# Ambient_Light_Sensor.net
KiCad netlist of a schematic drawn in Altium Designer
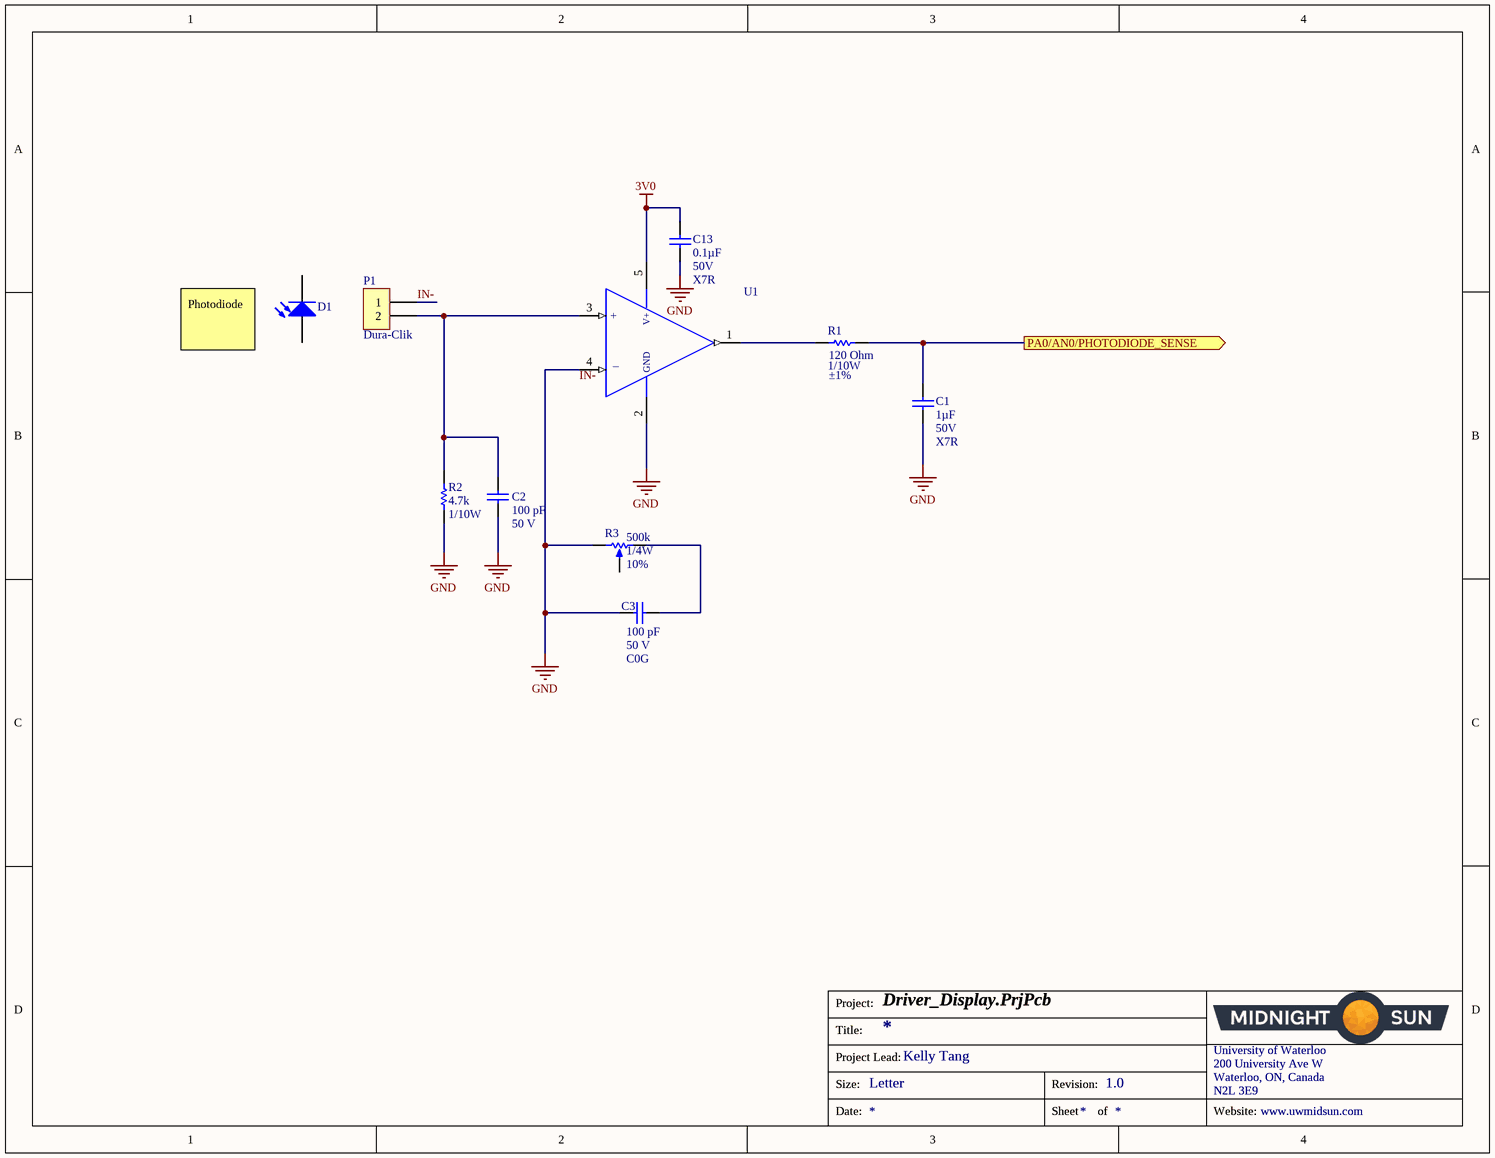
[diagram p0: Ambient Light Sensor.SchDoc]

(export (version "E")
  (design (tool "Eeschema 10.0.6"))
  (components
    (comp (ref "C1")
      (value "CAP CER 1UF 50V 10% X7R 0603")
      (footprint "CAP, 0603")
      (description "1µF ±10% 50V Ceramic Capacitor X7R 0603 (1608 Metric)")
      (fields
        (field (name "TOLERANCE") "±10%")
        (field (name "CAPACITANCE") "1µF")
        (field (name "VOLTAGE") "50V")
        (field (name "TEMPERATURE COEFFICIENT") "X7R")
      )
      (libsource (lib "Schematic Diagrams") (part "CAP CER 1UF 50V 10% X7R 0603"))
    )
    (comp (ref "C2")
      (value "CAP CER 100PF 50V C0G/NP0 0603")
      (footprint "CAP, 0603")
      (description "100pF ±1% 50V Ceramic Capacitor C0G, NP0 0603 (1608 Metric)")
      (fields
        (field (name "MANUFACTURER") "Kyocera AVX")
        (field (name "MANUFACTURER PART NUMBER") "06035A101FAT2A")
      )
      (libsource (lib "Schematic Diagrams") (part "CAP CER 100PF 50V C0G/NP0 0603"))
    )
    (comp (ref "C3")
      (value "CAP CER 100PF 50V C0G/NP0 0603")
      (footprint "CAP, 0603")
      (description "100pF ±1% 50V Ceramic Capacitor C0G, NP0 0603 (1608 Metric)")
      (fields
        (field (name "MANUFACTURER") "Kyocera AVX")
        (field (name "MANUFACTURER PART NUMBER") "06035A101FAT2A")
        (field (name "DIELECTRIC") "C0G")
      )
      (libsource (lib "Schematic Diagrams") (part "CAP CER 100PF 50V C0G/NP0 0603"))
    )
    (comp (ref "C13")
      (value "CAP CER 0.1UF 50V 10% X7R 0603")
      (footprint "CAP, 0603")
      (description "0.10µF ±10% 50V Ceramic Capacitor X7R 0603 (1608 Metric)")
      (fields
        (field (name "TOLERANCE") "±10%")
        (field (name "CAPACITANCE") "0.1µF")
        (field (name "VOLTAGE") "50V")
        (field (name "TEMPERATURE COEFFICIENT") "X7R")
      )
      (libsource (lib "Schematic Diagrams") (part "CAP CER 0.1UF 50V 10% X7R 0603"))
    )
    (comp (ref "D1")
      (value "DIODE 880NM W/FLTR THRUHOLE")
      (description "Photodiode 880nm 20ns 120° 2-DIP (0.213\", 5.40mm)")
      (fields (field (name "MANUFACTURER") "Osram Opto") (field (name "MANUFACTURER PART NUMBER") "BPW34FA"))
      (libsource (lib "Schematic Diagrams") (part "DIODE 880NM W/FLTR THRUHOLE"))
    )
    (comp (ref "P1")
      (value "Dura-Clik")
      (footprint "CONN, 2POS Dura-Click Vertical")
      (description "2 Positions Header, Shrouded Connector 0.079\" (2.00mm) Surface Mount, Vertical Tin")
      (fields
        (field (name "MANUFACTURER") "Molex, LLC")
        (field (name "MANUFACTURER PART NUMBER") "5600200220")
      )
      (libsource (lib "Schematic Diagrams") (part "CONN 2POS DURA-CLIK 0.079{dblquote} VERT"))
    )
    (comp (ref "R1")
      (value "RES 120 OHM 1% 1/10W 0603")
      (footprint "RES, 0603")
      (description "RES SMD 120 OHM 1% 1/10W 0603")
      (fields
        (field (name "TOLERANCE") "±1%")
        (field (name "RESISTANCE") "120 Ohm")
        (field (name "POWER") "1/10W")
      )
      (libsource (lib "Schematic Diagrams") (part "RES 120 OHM 1% 1/10W 0603"))
    )
    (comp (ref "R2")
      (value "RES 4.7K OHM 1% 1/10W 0603")
      (footprint "RES, 0603")
      (description "4.7k Ohm ±1% 0.1W, 1/10W Chip Resistor 0603 (1608 Metric) Moisture Resistant Thick Film")
      (fields
        (field (name "TOLERANCE") "±1%")
        (field (name "RESISTANCE (OHMS)") "4.7k")
        (field (name "POWER (WATTS)") "1/10W")
      )
      (libsource (lib "Schematic Diagrams") (part "RES 4.7K OHM 1% 1/10W 0603"))
    )
    (comp (ref "R3")
      (value "POT 500K OHM 0.25W SMD")
      (footprint "POT TRIMMER 500k")
      (description "500 kOhms 0.25W, 1/4W J Lead Surface Mount Trimmer Potentiometer Cermet 11 Turn Top Adjustment")
      (fields
        (field (name "MANUFACTURER") "Nidec Copal")
        (field (name "MANUFACTURER PART NUMBER") "SM-42TW504")
        (field (name "TOLERANCE") "10%")
        (field (name "MAX POWER DISSIPATION") "1/4W")
        (field (name "RESISTANCE") "500k")
      )
      (libsource (lib "Schematic Diagrams") (part "POT 500K OHM 0.25W SMD"))
    )
    (comp (ref "U1")
      (value "IC OP AMP GEN PURPOSE RR 10MHZ SOT-23-5")
      (footprint "IC OP AMP GP RR 10MHZ SOT-23-5")
      (description "General Purpose Amplifier 1 Circuit Rail-to-Rail SOT-23-5")
      (libsource (lib "Schematic Diagrams") (part "IC OP AMP GEN PURPOSE RR 10MHZ SOT-23-5"))
    )
  )
  (nets
    (net (code "1") (name "/IN-") (class "Default")
      (node (ref "P1") (pin "1") (pinfunction "1_1") (pintype "passive"))
    )
    (net (code "2") (name "/PA0{slash}AN0{slash}PHOTODIODE_SENSE") (class "Default")
      (node (ref "C1") (pin "1") (pinfunction "1_1") (pintype "passive"))
      (node (ref "R1") (pin "2") (pinfunction "2_2") (pintype "passive"))
    )
    (net (code "3") (name "3V0") (class "Default")
      (node (ref "C13") (pin "1") (pinfunction "1_1") (pintype "passive"))
      (node (ref "U1") (pin "5") (pinfunction "VDD_5") (pintype "power_in"))
    )
    (net (code "4") (name "GND") (class "Default")
      (node (ref "C1") (pin "2") (pinfunction "2_2") (pintype "passive"))
      (node (ref "C13") (pin "2") (pinfunction "2_2") (pintype "passive"))
      (node (ref "C2") (pin "2") (pinfunction "2_2") (pintype "passive"))
      (node (ref "C3") (pin "1") (pinfunction "1_1") (pintype "passive"))
      (node (ref "R2") (pin "1") (pinfunction "1_1") (pintype "passive"))
      (node (ref "R3") (pin "1") (pinfunction "TOP_1") (pintype "passive"))
      (node (ref "U1") (pin "2") (pinfunction "VSS_2") (pintype "power_in"))
      (node (ref "U1") (pin "4") (pinfunction "-IN_4") (pintype "input"))
    )
    (net (code "5") (name "Net-(R3-BOT)") (class "Default")
      (node (ref "C3") (pin "2") (pinfunction "2_2") (pintype "passive"))
      (node (ref "R3") (pin "3") (pinfunction "BOT_3") (pintype "passive"))
    )
    (net (code "6") (name "Net-(U1-+IN)") (class "Default")
      (node (ref "C2") (pin "1") (pinfunction "1_1") (pintype "passive"))
      (node (ref "P1") (pin "2") (pinfunction "2_2") (pintype "passive"))
      (node (ref "R2") (pin "2") (pinfunction "2_2") (pintype "passive"))
      (node (ref "U1") (pin "3") (pinfunction "+IN_3") (pintype "input"))
    )
    (net (code "7") (name "Net-(U1-OUTPUT)") (class "Default")
      (node (ref "R1") (pin "1") (pinfunction "1_1") (pintype "passive"))
      (node (ref "U1") (pin "1") (pinfunction "OUTPUT_1") (pintype "output"))
    )
    (net (code "8") (name "unconnected-(D1-A-Pad1)") (class "Default")
      (node (ref "D1") (pin "1") (pinfunction "A_1") (pintype "passive"))
    )
    (net (code "9") (name "unconnected-(D1-K-Pad2)") (class "Default")
      (node (ref "D1") (pin "2") (pinfunction "K_2") (pintype "passive"))
    )
    (net (code "10") (name "unconnected-(R3-TAP-Pad2)") (class "Default")
      (node (ref "R3") (pin "2") (pinfunction "TAP_2") (pintype "passive"))
    )
  )
)
